# power.net
KiCad netlist of a schematic drawn in Altium Designer
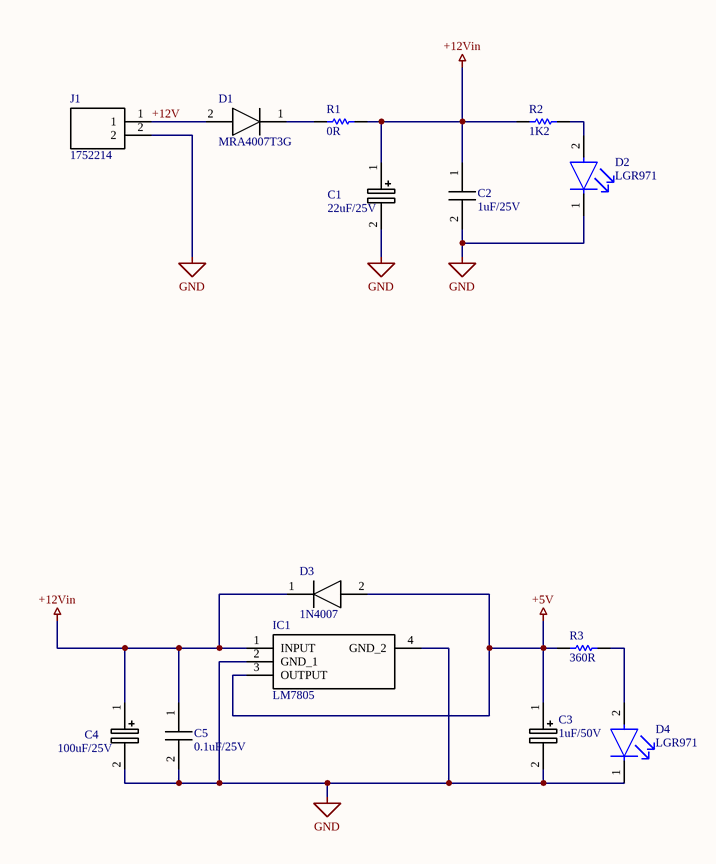
[diagram p0: power.SchDoc]

(export (version "E")
  (design (tool "Eeschema 10.0.6"))
  (components
    (comp (ref "C1")
      (value "22uF/25V")
      (footprint "SamacSys:CAPAE530X610N")
      (description "Capacitor Polarised")
      (fields
        (field (name "MANUFACTURER_PART_NUMBER") "APXG250ARA220ME61G")
        (field (name "MOUSER PART NUMBER") "661-APXG250A220ME61G")
      )
      (libsource (lib "*") (part "APXG250ARA220ME61G"))
    )
    (comp (ref "C2")
      (value "1uF/25V")
      (footprint "SamacSys:CAPC2012X70N")
      (description "Capacitor")
      (fields
        (field (name "MANUFACTURER_PART_NUMBER") "GRM216F51E104ZA01D")
        (field (name "MOUSER PART NUMBER") "81-GRM40Y104Z25D")
      )
      (libsource (lib "*") (part "GRM216F51E104ZA01D"))
    )
    (comp (ref "C3")
      (value "1uF/50V")
      (footprint "SamacSys:CAPAE430X550N")
      (description "Capacitor Polarised")
      (fields
        (field (name "MANUFACTURER_PART_NUMBER") "865060640001")
        (field (name "MOUSER PART NUMBER") "710-865060640001")
      )
      (libsource (lib "*") (part "865060640001"))
    )
    (comp (ref "C4")
      (value "100uF/25V")
      (footprint "SamacSys:CAPAE660X770N")
      (description "Capacitor Polarised")
      (fields
        (field (name "MANUFACTURER_PART_NUMBER") "865090445008")
        (field (name "MOUSER PART NUMBER") "710-865090445008")
      )
      (libsource (lib "*") (part "865090445008"))
    )
    (comp (ref "C5")
      (value "0.1uF/25V")
      (footprint "SamacSys:CAPC2012X70N")
      (description "Capacitor")
      (fields
        (field (name "MANUFACTURER_PART_NUMBER") "GRM216F51E104ZA01D")
        (field (name "MOUSER PART NUMBER") "81-GRM40Y104Z25D")
      )
      (libsource (lib "PIC12F675_prt") (part "GRM216F51E104ZA01D"))
    )
    (comp (ref "D1")
      (value "MRA4007T3G")
      (footprint "SamacSys:DIOM5226X220N")
      (description "Diode")
      (fields (field (name "MOUSER PART NUMBER") "863-MRA4007T3G"))
      (libsource (lib "*") (part "MRA4007T3G"))
    )
    (comp (ref "D2")
      (value "LGR971")
      (footprint "FP-LG_R971-MFG")
      (description "LED GREEN DIFFUSED 0805 SMD")
      (libsource (lib "Altium Content Vault") (part "8706943c75ba83719d021d2fdc84c58"))
    )
    (comp (ref "D3")
      (value "1N4007")
      (footprint "SamacSys:DIOM5027X244N")
      (description "Diode")
      (fields (field (name "MANUFACTURER_PART_NUMBER") "1n4007-SMD"))
      (libsource (lib "*") (part "1n4007-SMD"))
    )
    (comp (ref "D4")
      (value "LGR971")
      (footprint "FP-LG_R971-MFG")
      (description "LED GREEN DIFFUSED 0805 SMD")
      (libsource (lib "Altium Content Vault") (part "8706943c75ba83719d021d2fdc84c58"))
    )
    (comp (ref "IC1")
      (value "LM7805")
      (footprint "SamacSys:SOT230P700X180-4N")
      (description "Integrated Circuit")
      (fields
        (field (name "MANUFACTURER_PART_NUMBER") "LM7805MPX/NOPB")
        (field (name "MOUSER PART NUMBER") "595-LM7805MPX/NOPB")
      )
      (libsource (lib "*") (part "LM7805MPX_NOPB"))
    )
    (comp (ref "J1")
      (value "1752214")
      (footprint "SamacSys:1752214")
      (description "Connector")
      (fields (field (name "MOUSER PART NUMBER") "651-1752214"))
      (libsource (lib "*") (part "1752214"))
    )
    (comp (ref "R1")
      (value "0R")
      (footprint "RESC2013X55X40NL15T20")
      (fields (field (name "MANUFACTURER") "Vishay Dale") (field (name "PART NUMBER") "TNPW08052K00BEEN"))
      (libsource (lib "Altium Content Vault") (part "RES"))
    )
    (comp (ref "R2")
      (value "1K2")
      (footprint "RESC2013X55X40NL15T20")
      (fields (field (name "MANUFACTURER") "Vishay Dale") (field (name "PART NUMBER") "TNPW08052K00BEEN"))
      (libsource (lib "Altium Content Vault") (part "RES"))
    )
    (comp (ref "R3")
      (value "360R")
      (footprint "RESC2013X55X40NL15T20")
      (fields (field (name "MANUFACTURER") "Vishay Dale") (field (name "PART NUMBER") "TNPW08052K00BEEN"))
      (libsource (lib "Altium Content Vault") (part "RES"))
    )
  )
  (nets
    (net (code "1") (name "+5V") (class "Default")
      (node (ref "C3") (pin "1") (pinfunction "+_1") (pintype "passive"))
      (node (ref "D3") (pin "2") (pinfunction "A_2") (pintype "passive"))
      (node (ref "IC1") (pin "3") (pinfunction "OUTPUT_3") (pintype "passive"))
      (node (ref "R3") (pin "2") (pinfunction "2_2") (pintype "passive"))
    )
    (net (code "2") (name "+12Vin") (class "Default")
      (node (ref "C1") (pin "1") (pinfunction "+_1") (pintype "passive"))
      (node (ref "C2") (pin "1") (pinfunction "1_1") (pintype "passive"))
      (node (ref "C4") (pin "1") (pinfunction "+_1") (pintype "passive"))
      (node (ref "C5") (pin "1") (pinfunction "1_1") (pintype "passive"))
      (node (ref "D3") (pin "1") (pinfunction "K_1") (pintype "passive"))
      (node (ref "IC1") (pin "1") (pinfunction "INPUT_1") (pintype "passive"))
      (node (ref "R1") (pin "2") (pinfunction "2_2") (pintype "passive"))
      (node (ref "R2") (pin "2") (pinfunction "2_2") (pintype "passive"))
    )
    (net (code "3") (name "/+12V") (class "Default")
      (node (ref "D1") (pin "2") (pinfunction "A_2") (pintype "passive"))
      (node (ref "J1") (pin "1") (pinfunction "1_1") (pintype "passive"))
    )
    (net (code "4") (name "GND") (class "Default")
      (node (ref "C1") (pin "2") (pinfunction "-_2") (pintype "passive"))
      (node (ref "C2") (pin "2") (pinfunction "2_2") (pintype "passive"))
      (node (ref "C3") (pin "2") (pinfunction "-_2") (pintype "passive"))
      (node (ref "C4") (pin "2") (pinfunction "-_2") (pintype "passive"))
      (node (ref "C5") (pin "2") (pinfunction "2_2") (pintype "passive"))
      (node (ref "D2") (pin "1") (pinfunction "C_1") (pintype "passive"))
      (node (ref "D4") (pin "1") (pinfunction "C_1") (pintype "passive"))
      (node (ref "IC1") (pin "2") (pinfunction "GND_1_2") (pintype "passive"))
      (node (ref "IC1") (pin "4") (pinfunction "GND_2_4") (pintype "passive"))
      (node (ref "J1") (pin "2") (pinfunction "2_2") (pintype "passive"))
    )
    (net (code "5") (name "Net-(D1-K)") (class "Default")
      (node (ref "D1") (pin "1") (pinfunction "K_1") (pintype "passive"))
      (node (ref "R1") (pin "1") (pinfunction "1_1") (pintype "passive"))
    )
    (net (code "6") (name "Net-(D2-A)") (class "Default")
      (node (ref "D2") (pin "2") (pinfunction "A_2") (pintype "passive"))
      (node (ref "R2") (pin "1") (pinfunction "1_1") (pintype "passive"))
    )
    (net (code "7") (name "Net-(D4-A)") (class "Default")
      (node (ref "D4") (pin "2") (pinfunction "A_2") (pintype "passive"))
      (node (ref "R3") (pin "1") (pinfunction "1_1") (pintype "passive"))
    )
  )
)
